# Slave_BMS_ESKD.net
KiCad netlist of a schematic drawn in EAGLE
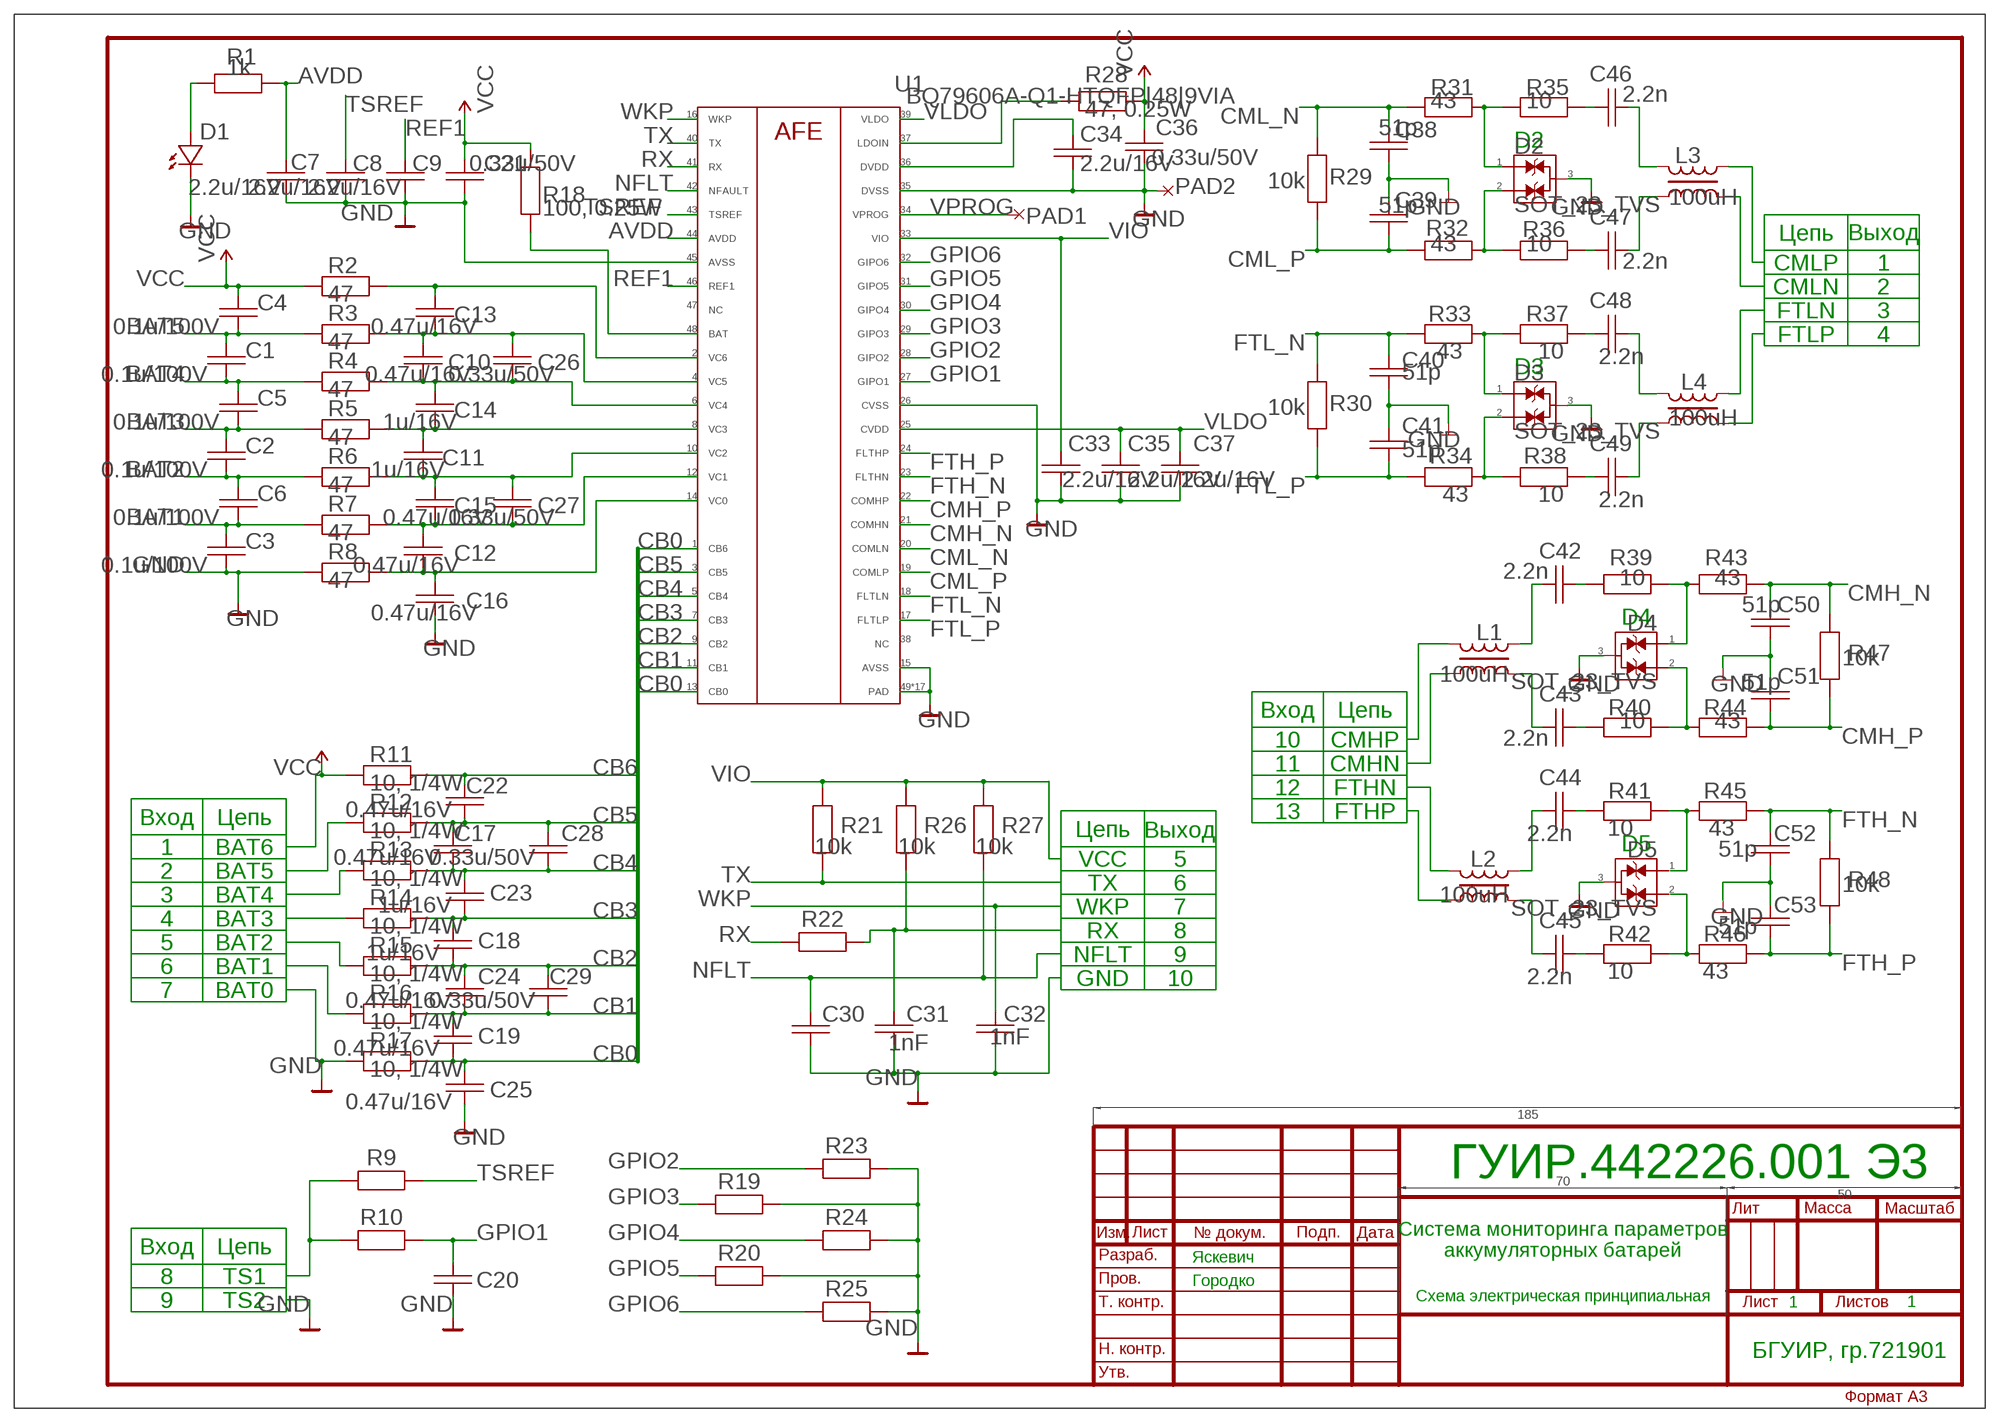
[diagram p0: schematic, sheet 1]

(export (version "E")
  (design (tool "Eeschema 10.0.6"))
  (components
    (comp (ref "C1")
      (value "0.1u/100V")
      (footprint "eagle-import:C1206")
      (libsource (lib "eagle-import") (part "ESCD_CAP"))
    )
    (comp (ref "C2")
      (value "0.1u/100V")
      (footprint "eagle-import:C1206")
      (libsource (lib "eagle-import") (part "ESCD_CAP"))
    )
    (comp (ref "C3")
      (value "0.1u/100V")
      (footprint "eagle-import:C1206")
      (libsource (lib "eagle-import") (part "ESCD_CAP"))
    )
    (comp (ref "C4")
      (value "0.1u/100V")
      (footprint "eagle-import:C1206")
      (libsource (lib "eagle-import") (part "ESCD_CAP"))
    )
    (comp (ref "C5")
      (value "0.1u/100V")
      (footprint "eagle-import:C1206")
      (libsource (lib "eagle-import") (part "ESCD_CAP"))
    )
    (comp (ref "C6")
      (value "0.1u/100V")
      (footprint "eagle-import:C1206")
      (libsource (lib "eagle-import") (part "ESCD_CAP"))
    )
    (comp (ref "C7")
      (value "2.2u/16V")
      (footprint "eagle-import:C1206")
      (libsource (lib "eagle-import") (part "ESCD_CAP"))
    )
    (comp (ref "C8")
      (value "2.2u/16V")
      (footprint "eagle-import:C1206")
      (libsource (lib "eagle-import") (part "ESCD_CAP"))
    )
    (comp (ref "C9")
      (value "2.2u/16V")
      (footprint "eagle-import:C1206")
      (libsource (lib "eagle-import") (part "ESCD_CAP"))
    )
    (comp (ref "C10")
      (value "0.47u/16V")
      (footprint "eagle-import:C1206")
      (libsource (lib "eagle-import") (part "ESCD_CAP"))
    )
    (comp (ref "C11")
      (value "1u/16V")
      (footprint "eagle-import:C1206")
      (libsource (lib "eagle-import") (part "ESCD_CAP"))
    )
    (comp (ref "C12")
      (value "0.47u/16V")
      (footprint "eagle-import:C1206")
      (libsource (lib "eagle-import") (part "ESCD_CAP"))
    )
    (comp (ref "C13")
      (value "0.47u/16V")
      (footprint "eagle-import:C1206")
      (libsource (lib "eagle-import") (part "ESCD_CAP"))
    )
    (comp (ref "C14")
      (value "1u/16V")
      (footprint "eagle-import:C1206")
      (libsource (lib "eagle-import") (part "ESCD_CAP"))
    )
    (comp (ref "C15")
      (value "0.47u/16V")
      (footprint "eagle-import:C1206")
      (libsource (lib "eagle-import") (part "ESCD_CAP"))
    )
    (comp (ref "C16")
      (value "0.47u/16V")
      (footprint "eagle-import:C1206")
      (libsource (lib "eagle-import") (part "ESCD_CAP"))
    )
    (comp (ref "C17")
      (value "0.47u/16V")
      (footprint "eagle-import:C1206")
      (libsource (lib "eagle-import") (part "ESCD_CAP"))
    )
    (comp (ref "C18")
      (value "1u/16V")
      (footprint "eagle-import:C1206")
      (libsource (lib "eagle-import") (part "ESCD_CAP"))
    )
    (comp (ref "C19")
      (value "0.47u/16V")
      (footprint "eagle-import:C1206")
      (libsource (lib "eagle-import") (part "ESCD_CAP"))
    )
    (comp (ref "C20")
      (value "ESCD_CAP")
      (footprint "eagle-import:C1206")
      (libsource (lib "eagle-import") (part "ESCD_CAP"))
    )
    (comp (ref "C21")
      (value "0.33u/50V")
      (footprint "eagle-import:C1206")
      (libsource (lib "eagle-import") (part "ESCD_CAP"))
    )
    (comp (ref "C22")
      (value "0.47u/16V")
      (footprint "eagle-import:C1206")
      (libsource (lib "eagle-import") (part "ESCD_CAP"))
    )
    (comp (ref "C23")
      (value "1u/16V")
      (footprint "eagle-import:C1206")
      (libsource (lib "eagle-import") (part "ESCD_CAP"))
    )
    (comp (ref "C24")
      (value "0.47u/16V")
      (footprint "eagle-import:C1206")
      (libsource (lib "eagle-import") (part "ESCD_CAP"))
    )
    (comp (ref "C25")
      (value "0.47u/16V")
      (footprint "eagle-import:C1206")
      (libsource (lib "eagle-import") (part "ESCD_CAP"))
    )
    (comp (ref "C26")
      (value "0.33u/50V")
      (footprint "eagle-import:C1206")
      (libsource (lib "eagle-import") (part "ESCD_CAP"))
    )
    (comp (ref "C27")
      (value "0.33u/50V")
      (footprint "eagle-import:C1206")
      (libsource (lib "eagle-import") (part "ESCD_CAP"))
    )
    (comp (ref "C28")
      (value "0.33u/50V")
      (footprint "eagle-import:C1206")
      (libsource (lib "eagle-import") (part "ESCD_CAP"))
    )
    (comp (ref "C29")
      (value "0.33u/50V")
      (footprint "eagle-import:C1206")
      (libsource (lib "eagle-import") (part "ESCD_CAP"))
    )
    (comp (ref "C30")
      (value "ESCD_CAP")
      (footprint "eagle-import:C1206")
      (libsource (lib "eagle-import") (part "ESCD_CAP"))
    )
    (comp (ref "C31")
      (value "1nF")
      (footprint "eagle-import:C1206")
      (libsource (lib "eagle-import") (part "ESCD_CAP"))
    )
    (comp (ref "C32")
      (value "1nF")
      (footprint "eagle-import:C1206")
      (libsource (lib "eagle-import") (part "ESCD_CAP"))
    )
    (comp (ref "C33")
      (value "2.2u/16V")
      (footprint "eagle-import:C1206")
      (libsource (lib "eagle-import") (part "ESCD_CAP"))
    )
    (comp (ref "C34")
      (value "2.2u/16V")
      (footprint "eagle-import:C1206")
      (libsource (lib "eagle-import") (part "ESCD_CAP"))
    )
    (comp (ref "C35")
      (value "2.2u/16V")
      (footprint "eagle-import:C1206")
      (libsource (lib "eagle-import") (part "ESCD_CAP"))
    )
    (comp (ref "C36")
      (value "0.33u/50V")
      (footprint "eagle-import:C1206")
      (libsource (lib "eagle-import") (part "ESCD_CAP"))
    )
    (comp (ref "C37")
      (value "2.2u/16V")
      (footprint "eagle-import:C1206")
      (libsource (lib "eagle-import") (part "ESCD_CAP"))
    )
    (comp (ref "C38")
      (value "51p")
      (footprint "eagle-import:C1206")
      (libsource (lib "eagle-import") (part "ESCD_CAP"))
    )
    (comp (ref "C39")
      (value "51p")
      (footprint "eagle-import:C1206")
      (libsource (lib "eagle-import") (part "ESCD_CAP"))
    )
    (comp (ref "C40")
      (value "51p")
      (footprint "eagle-import:C1206")
      (libsource (lib "eagle-import") (part "ESCD_CAP"))
    )
    (comp (ref "C41")
      (value "51p")
      (footprint "eagle-import:C1206")
      (libsource (lib "eagle-import") (part "ESCD_CAP"))
    )
    (comp (ref "C42")
      (value "2.2n")
      (footprint "eagle-import:C1206")
      (libsource (lib "eagle-import") (part "ESCD_CAP"))
    )
    (comp (ref "C43")
      (value "2.2n")
      (footprint "eagle-import:C1206")
      (libsource (lib "eagle-import") (part "ESCD_CAP"))
    )
    (comp (ref "C44")
      (value "2.2n")
      (footprint "eagle-import:C1206")
      (libsource (lib "eagle-import") (part "ESCD_CAP"))
    )
    (comp (ref "C45")
      (value "2.2n")
      (footprint "eagle-import:C1206")
      (libsource (lib "eagle-import") (part "ESCD_CAP"))
    )
    (comp (ref "C46")
      (value "2.2n")
      (footprint "eagle-import:C1206")
      (libsource (lib "eagle-import") (part "ESCD_CAP"))
    )
    (comp (ref "C47")
      (value "2.2n")
      (footprint "eagle-import:C1206")
      (libsource (lib "eagle-import") (part "ESCD_CAP"))
    )
    (comp (ref "C48")
      (value "2.2n")
      (footprint "eagle-import:C1206")
      (libsource (lib "eagle-import") (part "ESCD_CAP"))
    )
    (comp (ref "C49")
      (value "2.2n")
      (footprint "eagle-import:C1206")
      (libsource (lib "eagle-import") (part "ESCD_CAP"))
    )
    (comp (ref "C50")
      (value "51p")
      (footprint "eagle-import:C1206")
      (libsource (lib "eagle-import") (part "ESCD_CAP"))
    )
    (comp (ref "C51")
      (value "51p")
      (footprint "eagle-import:C1206")
      (libsource (lib "eagle-import") (part "ESCD_CAP"))
    )
    (comp (ref "C52")
      (value "51p")
      (footprint "eagle-import:C1206")
      (libsource (lib "eagle-import") (part "ESCD_CAP"))
    )
    (comp (ref "C53")
      (value "51p")
      (footprint "eagle-import:C1206")
      (libsource (lib "eagle-import") (part "ESCD_CAP"))
    )
    (comp (ref "D1")
      (value "ESCD_LED")
      (footprint "eagle-import:SOD106A")
      (fields (field (name "MPN") "BYS10/45"))
      (libsource (lib "eagle-import") (part "ESCD_LED"))
    )
    (comp (ref "D2")
      (value "SOT_23_TVS")
      (footprint "eagle-import:SOT23")
      (libsource (lib "eagle-import") (part "SOT_23_TVS"))
    )
    (comp (ref "D3")
      (value "SOT_23_TVS")
      (footprint "eagle-import:SOT23")
      (libsource (lib "eagle-import") (part "SOT_23_TVS"))
    )
    (comp (ref "D4")
      (value "SOT_23_TVS")
      (footprint "eagle-import:SOT23")
      (libsource (lib "eagle-import") (part "SOT_23_TVS"))
    )
    (comp (ref "D5")
      (value "SOT_23_TVS")
      (footprint "eagle-import:SOT23")
      (libsource (lib "eagle-import") (part "SOT_23_TVS"))
    )
    (comp (ref "L1")
      (value "100uH")
      (footprint "eagle-import:ACT45B")
      (libsource (lib "eagle-import") (part "TDK_ACT45BIND_BOURNS_SRF4532-M"))
    )
    (comp (ref "L2")
      (value "100uH")
      (footprint "eagle-import:ACT45B")
      (libsource (lib "eagle-import") (part "TDK_ACT45BIND_BOURNS_SRF4532-M"))
    )
    (comp (ref "L3")
      (value "100uH")
      (footprint "eagle-import:ACT45B")
      (libsource (lib "eagle-import") (part "TDK_ACT45BIND_BOURNS_SRF4532-M"))
    )
    (comp (ref "L4")
      (value "100uH")
      (footprint "eagle-import:ACT45B")
      (libsource (lib "eagle-import") (part "TDK_ACT45BIND_BOURNS_SRF4532-M"))
    )
    (comp (ref "PAD1")
      (value "SMD_PAD")
      (footprint "eagle-import:SMD_PAD")
      (libsource (lib "eagle-import") (part "SMD_PAD"))
    )
    (comp (ref "PAD2")
      (value "SMD_PAD")
      (footprint "eagle-import:SMD_PAD")
      (libsource (lib "eagle-import") (part "SMD_PAD"))
    )
    (comp (ref "R1")
      (value "1k")
      (footprint "eagle-import:R1206")
      (libsource (lib "eagle-import") (part "ESCD_RES"))
    )
    (comp (ref "R2")
      (value "47")
      (footprint "eagle-import:R1206")
      (libsource (lib "eagle-import") (part "ESCD_RES"))
    )
    (comp (ref "R3")
      (value "47")
      (footprint "eagle-import:R1206")
      (libsource (lib "eagle-import") (part "ESCD_RES"))
    )
    (comp (ref "R4")
      (value "47")
      (footprint "eagle-import:R1206")
      (libsource (lib "eagle-import") (part "ESCD_RES"))
    )
    (comp (ref "R5")
      (value "47")
      (footprint "eagle-import:R1206")
      (libsource (lib "eagle-import") (part "ESCD_RES"))
    )
    (comp (ref "R6")
      (value "47")
      (footprint "eagle-import:R1206")
      (libsource (lib "eagle-import") (part "ESCD_RES"))
    )
    (comp (ref "R7")
      (value "47")
      (footprint "eagle-import:R1206")
      (libsource (lib "eagle-import") (part "ESCD_RES"))
    )
    (comp (ref "R8")
      (value "47")
      (footprint "eagle-import:R1206")
      (libsource (lib "eagle-import") (part "ESCD_RES"))
    )
    (comp (ref "R9")
      (value "ESCD_RES")
      (footprint "eagle-import:R1206")
      (libsource (lib "eagle-import") (part "ESCD_RES"))
    )
    (comp (ref "R10")
      (value "ESCD_RES")
      (footprint "eagle-import:R1206")
      (libsource (lib "eagle-import") (part "ESCD_RES"))
    )
    (comp (ref "R11")
      (value "10, 1/4W")
      (footprint "eagle-import:R1206")
      (libsource (lib "eagle-import") (part "ESCD_RES"))
    )
    (comp (ref "R12")
      (value "10, 1/4W")
      (footprint "eagle-import:R1206")
      (libsource (lib "eagle-import") (part "ESCD_RES"))
    )
    (comp (ref "R13")
      (value "10, 1/4W")
      (footprint "eagle-import:R1206")
      (libsource (lib "eagle-import") (part "ESCD_RES"))
    )
    (comp (ref "R14")
      (value "10, 1/4W")
      (footprint "eagle-import:R1206")
      (libsource (lib "eagle-import") (part "ESCD_RES"))
    )
    (comp (ref "R15")
      (value "10, 1/4W")
      (footprint "eagle-import:R1206")
      (libsource (lib "eagle-import") (part "ESCD_RES"))
    )
    (comp (ref "R16")
      (value "10, 1/4W")
      (footprint "eagle-import:R1206")
      (libsource (lib "eagle-import") (part "ESCD_RES"))
    )
    (comp (ref "R17")
      (value "10, 1/4W")
      (footprint "eagle-import:R1206")
      (libsource (lib "eagle-import") (part "ESCD_RES"))
    )
    (comp (ref "R18")
      (value "100, 0.25W")
      (footprint "eagle-import:R1206")
      (libsource (lib "eagle-import") (part "ESCD_RES"))
    )
    (comp (ref "R19")
      (value "ESCD_RES")
      (footprint "eagle-import:R1206")
      (libsource (lib "eagle-import") (part "ESCD_RES"))
    )
    (comp (ref "R20")
      (value "ESCD_RES")
      (footprint "eagle-import:R1206")
      (libsource (lib "eagle-import") (part "ESCD_RES"))
    )
    (comp (ref "R21")
      (value "10k")
      (footprint "eagle-import:R1206")
      (libsource (lib "eagle-import") (part "ESCD_RES"))
    )
    (comp (ref "R22")
      (value "ESCD_RES")
      (footprint "eagle-import:R1206")
      (libsource (lib "eagle-import") (part "ESCD_RES"))
    )
    (comp (ref "R23")
      (value "ESCD_RES")
      (footprint "eagle-import:R1206")
      (libsource (lib "eagle-import") (part "ESCD_RES"))
    )
    (comp (ref "R24")
      (value "ESCD_RES")
      (footprint "eagle-import:R1206")
      (libsource (lib "eagle-import") (part "ESCD_RES"))
    )
    (comp (ref "R25")
      (value "ESCD_RES")
      (footprint "eagle-import:R1206")
      (libsource (lib "eagle-import") (part "ESCD_RES"))
    )
    (comp (ref "R26")
      (value "10k")
      (footprint "eagle-import:R1206")
      (libsource (lib "eagle-import") (part "ESCD_RES"))
    )
    (comp (ref "R27")
      (value "10k")
      (footprint "eagle-import:R1206")
      (libsource (lib "eagle-import") (part "ESCD_RES"))
    )
    (comp (ref "R28")
      (value "47, 0.25W")
      (footprint "eagle-import:R1206")
      (libsource (lib "eagle-import") (part "ESCD_RES"))
    )
    (comp (ref "R29")
      (value "10k")
      (footprint "eagle-import:R1206")
      (libsource (lib "eagle-import") (part "ESCD_RES"))
    )
    (comp (ref "R30")
      (value "10k")
      (footprint "eagle-import:R1206")
      (libsource (lib "eagle-import") (part "ESCD_RES"))
    )
    (comp (ref "R31")
      (value "43")
      (footprint "eagle-import:R1206")
      (libsource (lib "eagle-import") (part "ESCD_RES"))
    )
    (comp (ref "R32")
      (value "43")
      (footprint "eagle-import:R1206")
      (libsource (lib "eagle-import") (part "ESCD_RES"))
    )
    (comp (ref "R33")
      (value "43")
      (footprint "eagle-import:R1206")
      (libsource (lib "eagle-import") (part "ESCD_RES"))
    )
    (comp (ref "R34")
      (value "43")
      (footprint "eagle-import:R1206")
      (libsource (lib "eagle-import") (part "ESCD_RES"))
    )
    (comp (ref "R35")
      (value "10")
      (footprint "eagle-import:R1206")
      (libsource (lib "eagle-import") (part "ESCD_RES"))
    )
    (comp (ref "R36")
      (value "10")
      (footprint "eagle-import:R1206")
      (libsource (lib "eagle-import") (part "ESCD_RES"))
    )
    (comp (ref "R37")
      (value "10")
      (footprint "eagle-import:R1206")
      (libsource (lib "eagle-import") (part "ESCD_RES"))
    )
    (comp (ref "R38")
      (value "10")
      (footprint "eagle-import:R1206")
      (libsource (lib "eagle-import") (part "ESCD_RES"))
    )
    (comp (ref "R39")
      (value "10")
      (footprint "eagle-import:R1206")
      (libsource (lib "eagle-import") (part "ESCD_RES"))
    )
    (comp (ref "R40")
      (value "10")
      (footprint "eagle-import:R1206")
      (libsource (lib "eagle-import") (part "ESCD_RES"))
    )
    (comp (ref "R41")
      (value "10")
      (footprint "eagle-import:R1206")
      (libsource (lib "eagle-import") (part "ESCD_RES"))
    )
    (comp (ref "R42")
      (value "10")
      (footprint "eagle-import:R1206")
      (libsource (lib "eagle-import") (part "ESCD_RES"))
    )
    (comp (ref "R43")
      (value "43")
      (footprint "eagle-import:R1206")
      (libsource (lib "eagle-import") (part "ESCD_RES"))
    )
    (comp (ref "R44")
      (value "43")
      (footprint "eagle-import:R1206")
      (libsource (lib "eagle-import") (part "ESCD_RES"))
    )
    (comp (ref "R45")
      (value "43")
      (footprint "eagle-import:R1206")
      (libsource (lib "eagle-import") (part "ESCD_RES"))
    )
    (comp (ref "R46")
      (value "43")
      (footprint "eagle-import:R1206")
      (libsource (lib "eagle-import") (part "ESCD_RES"))
    )
    (comp (ref "R47")
      (value "10k")
      (footprint "eagle-import:R1206")
      (libsource (lib "eagle-import") (part "ESCD_RES"))
    )
    (comp (ref "R48")
      (value "10k")
      (footprint "eagle-import:R1206")
      (libsource (lib "eagle-import") (part "ESCD_RES"))
    )
    (comp (ref "U1")
      (value "BQ79606A-Q1-HTQFP|48|9VIA")
      (footprint "eagle-import:HTQFP48-9X9MM-VIA")
      (libsource (lib "eagle-import") (part "BQ79606A-Q1-HTQFP|48|9VIA"))
    )
  )
  (nets
    (net (code "1") (name "/AVDD") (class "Default")
      (node (ref "C7") (pin "1") (pinfunction "1_1") (pintype "passive"))
      (node (ref "R1") (pin "2") (pinfunction "2_2") (pintype "passive"))
      (node (ref "U1") (pin "44") (pinfunction "AVDD_44") (pintype "output"))
    )
    (net (code "2") (name "/BAT1") (class "Default")
      (node (ref "C3") (pin "2") (pinfunction "2_2") (pintype "passive"))
      (node (ref "C6") (pin "1") (pinfunction "1_1") (pintype "passive"))
      (node (ref "R16") (pin "1") (pinfunction "1_1") (pintype "passive"))
      (node (ref "R7") (pin "1") (pinfunction "1_1") (pintype "passive"))
    )
    (net (code "3") (name "/BAT2") (class "Default")
      (node (ref "C2") (pin "1") (pinfunction "1_1") (pintype "passive"))
      (node (ref "C6") (pin "2") (pinfunction "2_2") (pintype "passive"))
      (node (ref "R15") (pin "1") (pinfunction "1_1") (pintype "passive"))
      (node (ref "R6") (pin "1") (pinfunction "1_1") (pintype "passive"))
    )
    (net (code "4") (name "/BAT3") (class "Default")
      (node (ref "C2") (pin "2") (pinfunction "2_2") (pintype "passive"))
      (node (ref "C5") (pin "1") (pinfunction "1_1") (pintype "passive"))
      (node (ref "R14") (pin "1") (pinfunction "1_1") (pintype "passive"))
      (node (ref "R5") (pin "1") (pinfunction "1_1") (pintype "passive"))
    )
    (net (code "5") (name "/BAT4") (class "Default")
      (node (ref "C1") (pin "1") (pinfunction "1_1") (pintype "passive"))
      (node (ref "C5") (pin "2") (pinfunction "2_2") (pintype "passive"))
      (node (ref "R13") (pin "1") (pinfunction "1_1") (pintype "passive"))
      (node (ref "R4") (pin "1") (pinfunction "1_1") (pintype "passive"))
    )
    (net (code "6") (name "/BAT5") (class "Default")
      (node (ref "C1") (pin "2") (pinfunction "2_2") (pintype "passive"))
      (node (ref "C4") (pin "1") (pinfunction "1_1") (pintype "passive"))
      (node (ref "R12") (pin "1") (pinfunction "1_1") (pintype "passive"))
      (node (ref "R3") (pin "1") (pinfunction "1_1") (pintype "passive"))
    )
    (net (code "7") (name "/CB0") (class "Default")
      (node (ref "C19") (pin "1") (pinfunction "1_1") (pintype "passive"))
      (node (ref "C25") (pin "2") (pinfunction "2_2") (pintype "passive"))
      (node (ref "R17") (pin "2") (pinfunction "2_2") (pintype "passive"))
      (node (ref "U1") (pin "1") (pinfunction "CB6_1") (pintype "bidirectional"))
      (node (ref "U1") (pin "13") (pinfunction "CB0_13") (pintype "bidirectional"))
    )
    (net (code "8") (name "/CB1") (class "Default")
      (node (ref "C19") (pin "2") (pinfunction "2_2") (pintype "passive"))
      (node (ref "C24") (pin "1") (pinfunction "1_1") (pintype "passive"))
      (node (ref "C29") (pin "1") (pinfunction "1_1") (pintype "passive"))
      (node (ref "R16") (pin "2") (pinfunction "2_2") (pintype "passive"))
      (node (ref "U1") (pin "11") (pinfunction "CB1_11") (pintype "bidirectional"))
    )
    (net (code "9") (name "/CB2") (class "Default")
      (node (ref "C18") (pin "1") (pinfunction "1_1") (pintype "passive"))
      (node (ref "C24") (pin "2") (pinfunction "2_2") (pintype "passive"))
      (node (ref "C29") (pin "2") (pinfunction "2_2") (pintype "passive"))
      (node (ref "R15") (pin "2") (pinfunction "2_2") (pintype "passive"))
      (node (ref "U1") (pin "9") (pinfunction "CB2_9") (pintype "bidirectional"))
    )
    (net (code "10") (name "/CB3") (class "Default")
      (node (ref "C18") (pin "2") (pinfunction "2_2") (pintype "passive"))
      (node (ref "C23") (pin "1") (pinfunction "1_1") (pintype "passive"))
      (node (ref "R14") (pin "2") (pinfunction "2_2") (pintype "passive"))
      (node (ref "U1") (pin "7") (pinfunction "CB3_7") (pintype "bidirectional"))
    )
    (net (code "11") (name "/CB4") (class "Default")
      (node (ref "C17") (pin "1") (pinfunction "1_1") (pintype "passive"))
      (node (ref "C23") (pin "2") (pinfunction "2_2") (pintype "passive"))
      (node (ref "C28") (pin "1") (pinfunction "1_1") (pintype "passive"))
      (node (ref "R13") (pin "2") (pinfunction "2_2") (pintype "passive"))
      (node (ref "U1") (pin "5") (pinfunction "CB4_5") (pintype "bidirectional"))
    )
    (net (code "12") (name "/CB5") (class "Default")
      (node (ref "C17") (pin "2") (pinfunction "2_2") (pintype "passive"))
      (node (ref "C22") (pin "1") (pinfunction "1_1") (pintype "passive"))
      (node (ref "C28") (pin "2") (pinfunction "2_2") (pintype "passive"))
      (node (ref "R12") (pin "2") (pinfunction "2_2") (pintype "passive"))
      (node (ref "U1") (pin "3") (pinfunction "CB5_3") (pintype "bidirectional"))
    )
    (net (code "13") (name "/CB6") (class "Default")
      (node (ref "C22") (pin "2") (pinfunction "2_2") (pintype "passive"))
      (node (ref "R11") (pin "2") (pinfunction "2_2") (pintype "passive"))
    )
    (net (code "14") (name "/CMH_N") (class "Default")
      (node (ref "C50") (pin "2") (pinfunction "2_2") (pintype "passive"))
      (node (ref "R43") (pin "1") (pinfunction "1_1") (pintype "passive"))
      (node (ref "R47") (pin "1") (pinfunction "1_1") (pintype "passive"))
      (node (ref "U1") (pin "21") (pinfunction "COMHN_21") (pintype "input"))
    )
    (net (code "15") (name "/CMH_P") (class "Default")
      (node (ref "C51") (pin "2") (pinfunction "2_2") (pintype "passive"))
      (node (ref "R44") (pin "1") (pinfunction "1_1") (pintype "passive"))
      (node (ref "R47") (pin "2") (pinfunction "2_2") (pintype "passive"))
      (node (ref "U1") (pin "22") (pinfunction "COMHP_22") (pintype "input"))
    )
    (net (code "16") (name "/CML_N") (class "Default")
      (node (ref "C38") (pin "2") (pinfunction "2_2") (pintype "passive"))
      (node (ref "R29") (pin "1") (pinfunction "1_1") (pintype "passive"))
      (node (ref "R31") (pin "1") (pinfunction "1_1") (pintype "passive"))
      (node (ref "U1") (pin "20") (pinfunction "COMLN_20") (pintype "output"))
    )
    (net (code "17") (name "/CML_P") (class "Default")
      (node (ref "C39") (pin "2") (pinfunction "2_2") (pintype "passive"))
      (node (ref "R29") (pin "2") (pinfunction "2_2") (pintype "passive"))
      (node (ref "R32") (pin "1") (pinfunction "1_1") (pintype "passive"))
      (node (ref "U1") (pin "19") (pinfunction "COMLP_19") (pintype "output"))
    )
    (net (code "18") (name "/FTH_N") (class "Default")
      (node (ref "C52") (pin "2") (pinfunction "2_2") (pintype "passive"))
      (node (ref "R45") (pin "1") (pinfunction "1_1") (pintype "passive"))
      (node (ref "R48") (pin "1") (pinfunction "1_1") (pintype "passive"))
      (node (ref "U1") (pin "23") (pinfunction "FLTHN_23") (pintype "input"))
    )
    (net (code "19") (name "/FTH_P") (class "Default")
      (node (ref "C53") (pin "2") (pinfunction "2_2") (pintype "passive"))
      (node (ref "R46") (pin "1") (pinfunction "1_1") (pintype "passive"))
      (node (ref "R48") (pin "2") (pinfunction "2_2") (pintype "passive"))
      (node (ref "U1") (pin "24") (pinfunction "FLTHP_24") (pintype "input"))
    )
    (net (code "20") (name "/FTL_N") (class "Default")
      (node (ref "C40") (pin "2") (pinfunction "2_2") (pintype "passive"))
      (node (ref "R30") (pin "1") (pinfunction "1_1") (pintype "passive"))
      (node (ref "R33") (pin "1") (pinfunction "1_1") (pintype "passive"))
      (node (ref "U1") (pin "18") (pinfunction "FLTLN_18") (pintype "output"))
    )
    (net (code "21") (name "/FTL_P") (class "Default")
      (node (ref "C41") (pin "2") (pinfunction "2_2") (pintype "passive"))
      (node (ref "R30") (pin "2") (pinfunction "2_2") (pintype "passive"))
      (node (ref "R34") (pin "1") (pinfunction "1_1") (pintype "passive"))
      (node (ref "U1") (pin "17") (pinfunction "FLTLP_17") (pintype "output"))
    )
    (net (code "22") (name "/GPIO1") (class "Default")
      (node (ref "C20") (pin "1") (pinfunction "1_1") (pintype "passive"))
      (node (ref "R10") (pin "2") (pinfunction "2_2") (pintype "passive"))
      (node (ref "U1") (pin "27") (pinfunction "GIPO1_27") (pintype "bidirectional"))
    )
    (net (code "23") (name "/GPIO2") (class "Default")
      (node (ref "R23") (pin "1") (pinfunction "1_1") (pintype "passive"))
      (node (ref "U1") (pin "28") (pinfunction "GIPO2_28") (pintype "bidirectional"))
    )
    (net (code "24") (name "/GPIO3") (class "Default")
      (node (ref "R19") (pin "1") (pinfunction "1_1") (pintype "passive"))
      (node (ref "U1") (pin "29") (pinfunction "GIPO3_29") (pintype "bidirectional"))
    )
    (net (code "25") (name "/GPIO4") (class "Default")
      (node (ref "R24") (pin "1") (pinfunction "1_1") (pintype "passive"))
      (node (ref "U1") (pin "30") (pinfunction "GIPO4_30") (pintype "bidirectional"))
    )
    (net (code "26") (name "/GPIO5") (class "Default")
      (node (ref "R20") (pin "1") (pinfunction "1_1") (pintype "passive"))
      (node (ref "U1") (pin "31") (pinfunction "GIPO5_31") (pintype "bidirectional"))
    )
    (net (code "27") (name "/GPIO6") (class "Default")
      (node (ref "R25") (pin "1") (pinfunction "1_1") (pintype "passive"))
      (node (ref "U1") (pin "32") (pinfunction "GIPO6_32") (pintype "bidirectional"))
    )
    (net (code "28") (name "/NFLT") (class "Default")
      (node (ref "C30") (pin "1") (pinfunction "1_1") (pintype "passive"))
      (node (ref "R27") (pin "1") (pinfunction "1_1") (pintype "passive"))
      (node (ref "U1") (pin "42") (pinfunction "NFAULT_42") (pintype "output"))
    )
    (net (code "29") (name "/REF1") (class "Default")
      (node (ref "C9") (pin "1") (pinfunction "1_1") (pintype "passive"))
      (node (ref "U1") (pin "46") (pinfunction "REF1_46") (pintype "output"))
    )
    (net (code "30") (name "/RX") (class "Default")
      (node (ref "R22") (pin "1") (pinfunction "1_1") (pintype "passive"))
      (node (ref "U1") (pin "41") (pinfunction "RX_41") (pintype "input"))
    )
    (net (code "31") (name "/TSREF") (class "Default")
      (node (ref "C8") (pin "1") (pinfunction "1_1") (pintype "passive"))
      (node (ref "R9") (pin "2") (pinfunction "2_2") (pintype "passive"))
      (node (ref "U1") (pin "43") (pinfunction "TSREF_43") (pintype "output"))
    )
    (net (code "32") (name "/TX") (class "Default")
      (node (ref "R21") (pin "1") (pinfunction "1_1") (pintype "passive"))
      (node (ref "U1") (pin "40") (pinfunction "TX_40") (pintype "output"))
    )
    (net (code "33") (name "/VIO") (class "Default")
      (node (ref "C33") (pin "1") (pinfunction "1_1") (pintype "passive"))
      (node (ref "R21") (pin "2") (pinfunction "2_2") (pintype "passive"))
      (node (ref "R26") (pin "2") (pinfunction "2_2") (pintype "passive"))
      (node (ref "R27") (pin "2") (pinfunction "2_2") (pintype "passive"))
      (node (ref "U1") (pin "33") (pinfunction "VIO_33") (pintype "input"))
    )
    (net (code "34") (name "/VLDO") (class "Default")
      (node (ref "C35") (pin "1") (pinfunction "1_1") (pintype "passive"))
      (node (ref "C37") (pin "1") (pinfunction "1_1") (pintype "passive"))
      (node (ref "U1") (pin "25") (pinfunction "CVDD_25") (pintype "power_in"))
      (node (ref "U1") (pin "39") (pinfunction "VLDO_39") (pintype "output"))
    )
    (net (code "35") (name "/VPROG") (class "Default")
      (node (ref "PAD1") (pin "1") (pinfunction "P_1") (pintype "passive"))
      (node (ref "U1") (pin "34") (pinfunction "VPROG_34") (pintype "input"))
    )
    (net (code "36") (name "/WKP") (class "Default")
      (node (ref "C32") (pin "2") (pinfunction "2_2") (pintype "passive"))
      (node (ref "U1") (pin "16") (pinfunction "WKP_16") (pintype "input"))
    )
    (net (code "37") (name "GND") (class "Default")
      (node (ref "C16") (pin "1") (pinfunction "1_1") (pintype "passive"))
      (node (ref "C20") (pin "2") (pinfunction "2_2") (pintype "passive"))
      (node (ref "C21") (pin "2") (pinfunction "2_2") (pintype "passive"))
      (node (ref "C25") (pin "1") (pinfunction "1_1") (pintype "passive"))
      (node (ref "C3") (pin "1") (pinfunction "1_1") (pintype "passive"))
      (node (ref "C30") (pin "2") (pinfunction "2_2") (pintype "passive"))
      (node (ref "C31") (pin "1") (pinfunction "1_1") (pintype "passive"))
      (node (ref "C32") (pin "1") (pinfunction "1_1") (pintype "passive"))
      (node (ref "C33") (pin "2") (pinfunction "2_2") (pintype "passive"))
      (node (ref "C34") (pin "2") (pinfunction "2_2") (pintype "passive"))
      (node (ref "C35") (pin "2") (pinfunction "2_2") (pintype "passive"))
      (node (ref "C36") (pin "2") (pinfunction "2_2") (pintype "passive"))
      (node (ref "C37") (pin "2") (pinfunction "2_2") (pintype "passive"))
      (node (ref "C38") (pin "1") (pinfunction "1_1") (pintype "passive"))
      (node (ref "C39") (pin "1") (pinfunction "1_1") (pintype "passive"))
      (node (ref "C40") (pin "1") (pinfunction "1_1") (pintype "passive"))
      (node (ref "C41") (pin "1") (pinfunction "1_1") (pintype "passive"))
      (node (ref "C50") (pin "1") (pinfunction "1_1") (pintype "passive"))
      (node (ref "C51") (pin "1") (pinfunction "1_1") (pintype "passive"))
      (node (ref "C52") (pin "1") (pinfunction "1_1") (pintype "passive"))
      (node (ref "C53") (pin "1") (pinfunction "1_1") (pintype "passive"))
      (node (ref "C7") (pin "2") (pinfunction "2_2") (pintype "passive"))
      (node (ref "C8") (pin "2") (pinfunction "2_2") (pintype "passive"))
      (node (ref "C9") (pin "2") (pinfunction "2_2") (pintype "passive"))
      (node (ref "D1") (pin "K") (pinfunction "K_K") (pintype "passive"))
      (node (ref "D2") (pin "3") (pinfunction "3_3") (pintype "passive"))
      (node (ref "D3") (pin "3") (pinfunction "3_3") (pintype "passive"))
      (node (ref "D4") (pin "3") (pinfunction "3_3") (pintype "passive"))
      (node (ref "D5") (pin "3") (pinfunction "3_3") (pintype "passive"))
      (node (ref "PAD2") (pin "1") (pinfunction "P_1") (pintype "passive"))
      (node (ref "R17") (pin "1") (pinfunction "1_1") (pintype "passive"))
      (node (ref "R19") (pin "2") (pinfunction "2_2") (pintype "passive"))
      (node (ref "R20") (pin "2") (pinfunction "2_2") (pintype "passive"))
      (node (ref "R23") (pin "2") (pinfunction "2_2") (pintype "passive"))
      (node (ref "R24") (pin "2") (pinfunction "2_2") (pintype "passive"))
      (node (ref "R25") (pin "2") (pinfunction "2_2") (pintype "passive"))
      (node (ref "R8") (pin "1") (pinfunction "1_1") (pintype "passive"))
      (node (ref "U1") (pin "15") (pinfunction "AVSS_15") (pintype "power_in"))
      (node (ref "U1") (pin "26") (pinfunction "CVSS_26") (pintype "power_in"))
      (node (ref "U1") (pin "35") (pinfunction "DVSS_35") (pintype "power_in"))
      (node (ref "U1") (pin "45") (pinfunction "AVSS_45") (pintype "power_in"))
      (node (ref "U1") (pin "49") (pinfunction "PAD_49") (pintype "power_in"))
      (node (ref "U1") (pin "491") (pinfunction "PAD_491") (pintype "power_in"))
      (node (ref "U1") (pin "492") (pinfunction "PAD_492") (pintype "power_in"))
      (node (ref "U1") (pin "493") (pinfunction "PAD_493") (pintype "power_in"))
      (node (ref "U1") (pin "494") (pinfunction "PAD_494") (pintype "power_in"))
      (node (ref "U1") (pin "495") (pinfunction "PAD_495") (pintype "power_in"))
      (node (ref "U1") (pin "496") (pinfunction "PAD_496") (pintype "power_in"))
      (node (ref "U1") (pin "497") (pinfunction "PAD_497") (pintype "power_in"))
      (node (ref "U1") (pin "498") (pinfunction "PAD_498") (pintype "power_in"))
      (node (ref "U1") (pin "499") (pinfunction "PAD_499") (pintype "power_in"))
      (node (ref "U1") (pin "P$1") (pinfunction "PAD_P$1") (pintype "power_in"))
      (node (ref "U1") (pin "P$2") (pinfunction "PAD_P$2") (pintype "power_in"))
      (node (ref "U1") (pin "P$3") (pinfunction "PAD_P$3") (pintype "power_in"))
      (node (ref "U1") (pin "P$4") (pinfunction "PAD_P$4") (pintype "power_in"))
      (node (ref "U1") (pin "P$5") (pinfunction "PAD_P$5") (pintype "power_in"))
      (node (ref "U1") (pin "P$6") (pinfunction "PAD_P$6") (pintype "power_in"))
      (node (ref "U1") (pin "P$7") (pinfunction "PAD_P$7") (pintype "power_in"))
    )
    (net (code "38") (name "Net-(C31-Pad2)") (class "Default")
      (node (ref "C31") (pin "2") (pinfunction "2_2") (pintype "passive"))
      (node (ref "R22") (pin "2") (pinfunction "2_2") (pintype "passive"))
      (node (ref "R26") (pin "1") (pinfunction "1_1") (pintype "passive"))
    )
    (net (code "39") (name "Net-(C42-Pad1)") (class "Default")
      (node (ref "C42") (pin "1") (pinfunction "1_1") (pintype "passive"))
      (node (ref "L1") (pin "1") (pinfunction "1_1") (pintype "passive"))
    )
    (net (code "40") (name "Net-(C42-Pad2)") (class "Default")
      (node (ref "C42") (pin "2") (pinfunction "2_2") (pintype "passive"))
      (node (ref "R39") (pin "2") (pinfunction "2_2") (pintype "passive"))
    )
    (net (code "41") (name "Net-(C43-Pad1)") (class "Default")
      (node (ref "C43") (pin "1") (pinfunction "1_1") (pintype "passive"))
      (node (ref "L1") (pin "2") (pinfunction "2_2") (pintype "passive"))
    )
    (net (code "42") (name "Net-(C43-Pad2)") (class "Default")
      (node (ref "C43") (pin "2") (pinfunction "2_2") (pintype "passive"))
      (node (ref "R40") (pin "2") (pinfunction "2_2") (pintype "passive"))
    )
    (net (code "43") (name "Net-(C44-Pad1)") (class "Default")
      (node (ref "C44") (pin "1") (pinfunction "1_1") (pintype "passive"))
      (node (ref "L2") (pin "1") (pinfunction "1_1") (pintype "passive"))
    )
    (net (code "44") (name "Net-(C44-Pad2)") (class "Default")
      (node (ref "C44") (pin "2") (pinfunction "2_2") (pintype "passive"))
      (node (ref "R41") (pin "2") (pinfunction "2_2") (pintype "passive"))
    )
    (net (code "45") (name "Net-(C45-Pad1)") (class "Default")
      (node (ref "C45") (pin "1") (pinfunction "1_1") (pintype "passive"))
      (node (ref "L2") (pin "2") (pinfunction "2_2") (pintype "passive"))
    )
    (net (code "46") (name "Net-(C45-Pad2)") (class "Default")
      (node (ref "C45") (pin "2") (pinfunction "2_2") (pintype "passive"))
      (node (ref "R42") (pin "2") (pinfunction "2_2") (pintype "passive"))
    )
    (net (code "47") (name "Net-(C46-Pad1)") (class "Default")
      (node (ref "C46") (pin "1") (pinfunction "1_1") (pintype "passive"))
      (node (ref "L3") (pin "1") (pinfunction "1_1") (pintype "passive"))
    )
    (net (code "48") (name "Net-(C46-Pad2)") (class "Default")
      (node (ref "C46") (pin "2") (pinfunction "2_2") (pintype "passive"))
      (node (ref "R35") (pin "2") (pinfunction "2_2") (pintype "passive"))
    )
    (net (code "49") (name "Net-(C47-Pad1)") (class "Default")
      (node (ref "C47") (pin "1") (pinfunction "1_1") (pintype "passive"))
      (node (ref "L3") (pin "2") (pinfunction "2_2") (pintype "passive"))
    )
    (net (code "50") (name "Net-(C47-Pad2)") (class "Default")
      (node (ref "C47") (pin "2") (pinfunction "2_2") (pintype "passive"))
      (node (ref "R36") (pin "2") (pinfunction "2_2") (pintype "passive"))
    )
    (net (code "51") (name "Net-(C48-Pad1)") (class "Default")
      (node (ref "C48") (pin "1") (pinfunction "1_1") (pintype "passive"))
      (node (ref "L4") (pin "1") (pinfunction "1_1") (pintype "passive"))
    )
    (net (code "52") (name "Net-(C48-Pad2)") (class "Default")
      (node (ref "C48") (pin "2") (pinfunction "2_2") (pintype "passive"))
      (node (ref "R37") (pin "2") (pinfunction "2_2") (pintype "passive"))
    )
    (net (code "53") (name "Net-(C49-Pad1)") (class "Default")
      (node (ref "C49") (pin "1") (pinfunction "1_1") (pintype "passive"))
      (node (ref "L4") (pin "2") (pinfunction "2_2") (pintype "passive"))
    )
    (net (code "54") (name "Net-(C49-Pad2)") (class "Default")
      (node (ref "C49") (pin "2") (pinfunction "2_2") (pintype "passive"))
      (node (ref "R38") (pin "2") (pinfunction "2_2") (pintype "passive"))
    )
    (net (code "55") (name "Net-(D1-PadA)") (class "Default")
      (node (ref "D1") (pin "A") (pinfunction "A_A") (pintype "passive"))
      (node (ref "R1") (pin "1") (pinfunction "1_1") (pintype "passive"))
    )
    (net (code "56") (name "Net-(D2-Pad1)") (class "Default")
      (node (ref "D2") (pin "1") (pinfunction "1_1") (pintype "passive"))
      (node (ref "R31") (pin "2") (pinfunction "2_2") (pintype "passive"))
      (node (ref "R35") (pin "1") (pinfunction "1_1") (pintype "passive"))
    )
    (net (code "57") (name "Net-(D2-Pad2)") (class "Default")
      (node (ref "D2") (pin "2") (pinfunction "2_2") (pintype "passive"))
      (node (ref "R32") (pin "2") (pinfunction "2_2") (pintype "passive"))
      (node (ref "R36") (pin "1") (pinfunction "1_1") (pintype "passive"))
    )
    (net (code "58") (name "Net-(D4-Pad1)") (class "Default")
      (node (ref "D4") (pin "1") (pinfunction "1_1") (pintype "passive"))
      (node (ref "R39") (pin "1") (pinfunction "1_1") (pintype "passive"))
      (node (ref "R43") (pin "2") (pinfunction "2_2") (pintype "passive"))
    )
    (net (code "59") (name "Net-(D4-Pad2)") (class "Default")
      (node (ref "D4") (pin "2") (pinfunction "2_2") (pintype "passive"))
      (node (ref "R40") (pin "1") (pinfunction "1_1") (pintype "passive"))
      (node (ref "R44") (pin "2") (pinfunction "2_2") (pintype "passive"))
    )
    (net (code "60") (name "Net-(R10-Pad1)") (class "Default")
      (node (ref "R10") (pin "1") (pinfunction "1_1") (pintype "passive"))
      (node (ref "R9") (pin "1") (pinfunction "1_1") (pintype "passive"))
    )
    (net (code "61") (name "Net-(R33-Pad2)") (class "Default")
      (node (ref "R33") (pin "2") (pinfunction "2_2") (pintype "passive"))
      (node (ref "R37") (pin "1") (pinfunction "1_1") (pintype "passive"))
    )
    (net (code "62") (name "Net-(R34-Pad2)") (class "Default")
      (node (ref "R34") (pin "2") (pinfunction "2_2") (pintype "passive"))
      (node (ref "R38") (pin "1") (pinfunction "1_1") (pintype "passive"))
    )
    (net (code "63") (name "Net-(R41-Pad1)") (class "Default")
      (node (ref "R41") (pin "1") (pinfunction "1_1") (pintype "passive"))
      (node (ref "R45") (pin "2") (pinfunction "2_2") (pintype "passive"))
    )
    (net (code "64") (name "Net-(R42-Pad1)") (class "Default")
      (node (ref "R42") (pin "1") (pinfunction "1_1") (pintype "passive"))
      (node (ref "R46") (pin "2") (pinfunction "2_2") (pintype "passive"))
    )
    (net (code "65") (name "Net-(U1-BAT)") (class "Default")
      (node (ref "R18") (pin "1") (pinfunction "1_1") (pintype "passive"))
      (node (ref "U1") (pin "48") (pinfunction "BAT_48") (pintype "input"))
    )
    (net (code "66") (name "Net-(U1-DVDD)") (class "Default")
      (node (ref "C34") (pin "1") (pinfunction "1_1") (pintype "passive"))
      (node (ref "U1") (pin "36") (pinfunction "DVDD_36") (pintype "power_in"))
    )
    (net (code "67") (name "Net-(U1-LDOIN)") (class "Default")
      (node (ref "R28") (pin "1") (pinfunction "1_1") (pintype "passive"))
      (node (ref "U1") (pin "37") (pinfunction "LDOIN_37") (pintype "input"))
    )
    (net (code "68") (name "Net-(U1-VC0)") (class "Default")
      (node (ref "C12") (pin "1") (pinfunction "1_1") (pintype "passive"))
      (node (ref "C16") (pin "2") (pinfunction "2_2") (pintype "passive"))
      (node (ref "R8") (pin "2") (pinfunction "2_2") (pintype "passive"))
      (node (ref "U1") (pin "14") (pinfunction "VC0_14") (pintype "input"))
    )
    (net (code "69") (name "Net-(U1-VC1)") (class "Default")
      (node (ref "C12") (pin "2") (pinfunction "2_2") (pintype "passive"))
      (node (ref "C15") (pin "1") (pinfunction "1_1") (pintype "passive"))
      (node (ref "C27") (pin "1") (pinfunction "1_1") (pintype "passive"))
      (node (ref "R7") (pin "2") (pinfunction "2_2") (pintype "passive"))
      (node (ref "U1") (pin "12") (pinfunction "VC1_12") (pintype "input"))
    )
    (net (code "70") (name "Net-(U1-VC2)") (class "Default")
      (node (ref "C11") (pin "1") (pinfunction "1_1") (pintype "passive"))
      (node (ref "C15") (pin "2") (pinfunction "2_2") (pintype "passive"))
      (node (ref "C27") (pin "2") (pinfunction "2_2") (pintype "passive"))
      (node (ref "R6") (pin "2") (pinfunction "2_2") (pintype "passive"))
      (node (ref "U1") (pin "10") (pinfunction "VC2_10") (pintype "input"))
    )
    (net (code "71") (name "Net-(U1-VC3)") (class "Default")
      (node (ref "C11") (pin "2") (pinfunction "2_2") (pintype "passive"))
      (node (ref "C14") (pin "1") (pinfunction "1_1") (pintype "passive"))
      (node (ref "R5") (pin "2") (pinfunction "2_2") (pintype "passive"))
      (node (ref "U1") (pin "8") (pinfunction "VC3_8") (pintype "input"))
    )
    (net (code "72") (name "Net-(U1-VC4)") (class "Default")
      (node (ref "C10") (pin "1") (pinfunction "1_1") (pintype "passive"))
      (node (ref "C14") (pin "2") (pinfunction "2_2") (pintype "passive"))
      (node (ref "C26") (pin "1") (pinfunction "1_1") (pintype "passive"))
      (node (ref "R4") (pin "2") (pinfunction "2_2") (pintype "passive"))
      (node (ref "U1") (pin "6") (pinfunction "VC4_6") (pintype "input"))
    )
    (net (code "73") (name "Net-(U1-VC5)") (class "Default")
      (node (ref "C10") (pin "2") (pinfunction "2_2") (pintype "passive"))
      (node (ref "C13") (pin "1") (pinfunction "1_1") (pintype "passive"))
      (node (ref "C26") (pin "2") (pinfunction "2_2") (pintype "passive"))
      (node (ref "R3") (pin "2") (pinfunction "2_2") (pintype "passive"))
      (node (ref "U1") (pin "4") (pinfunction "VC5_4") (pintype "input"))
    )
    (net (code "74") (name "Net-(U1-VC6)") (class "Default")
      (node (ref "C13") (pin "2") (pinfunction "2_2") (pintype "passive"))
      (node (ref "R2") (pin "2") (pinfunction "2_2") (pintype "passive"))
      (node (ref "U1") (pin "2") (pinfunction "VC6_2") (pintype "input"))
    )
    (net (code "75") (name "VCC") (class "Default")
      (node (ref "C21") (pin "1") (pinfunction "1_1") (pintype "passive"))
      (node (ref "C36") (pin "1") (pinfunction "1_1") (pintype "passive"))
      (node (ref "C4") (pin "2") (pinfunction "2_2") (pintype "passive"))
      (node (ref "R11") (pin "1") (pinfunction "1_1") (pintype "passive"))
      (node (ref "R18") (pin "2") (pinfunction "2_2") (pintype "passive"))
      (node (ref "R2") (pin "1") (pinfunction "1_1") (pintype "passive"))
      (node (ref "R28") (pin "2") (pinfunction "2_2") (pintype "passive"))
    )
    (net (code "76") (name "unconnected-(D3-Pad1)") (class "Default")
      (node (ref "D3") (pin "1") (pinfunction "1_1") (pintype "passive"))
    )
    (net (code "77") (name "unconnected-(D3-Pad2)") (class "Default")
      (node (ref "D3") (pin "2") (pinfunction "2_2") (pintype "passive"))
    )
    (net (code "78") (name "unconnected-(D5-Pad1)") (class "Default")
      (node (ref "D5") (pin "1") (pinfunction "1_1") (pintype "passive"))
    )
    (net (code "79") (name "unconnected-(D5-Pad2)") (class "Default")
      (node (ref "D5") (pin "2") (pinfunction "2_2") (pintype "passive"))
    )
    (net (code "80") (name "unconnected-(L1-Pad3)") (class "Default")
      (node (ref "L1") (pin "3") (pinfunction "3_3") (pintype "passive"))
    )
    (net (code "81") (name "unconnected-(L1-Pad4)") (class "Default")
      (node (ref "L1") (pin "4") (pinfunction "4_4") (pintype "passive"))
    )
    (net (code "82") (name "unconnected-(L2-Pad3)") (class "Default")
      (node (ref "L2") (pin "3") (pinfunction "3_3") (pintype "passive"))
    )
    (net (code "83") (name "unconnected-(L2-Pad4)") (class "Default")
      (node (ref "L2") (pin "4") (pinfunction "4_4") (pintype "passive"))
    )
    (net (code "84") (name "unconnected-(L3-Pad3)") (class "Default")
      (node (ref "L3") (pin "3") (pinfunction "3_3") (pintype "passive"))
    )
    (net (code "85") (name "unconnected-(L3-Pad4)") (class "Default")
      (node (ref "L3") (pin "4") (pinfunction "4_4") (pintype "passive"))
    )
    (net (code "86") (name "unconnected-(L4-Pad3)") (class "Default")
      (node (ref "L4") (pin "3") (pinfunction "3_3") (pintype "passive"))
    )
    (net (code "87") (name "unconnected-(L4-Pad4)") (class "Default")
      (node (ref "L4") (pin "4") (pinfunction "4_4") (pintype "passive"))
    )
    (net (code "88") (name "unconnected-(U1-NC-Pad38)") (class "Default")
      (node (ref "U1") (pin "38") (pinfunction "NC_38") (pintype "no_connect"))
    )
    (net (code "89") (name "unconnected-(U1-NC-Pad47)") (class "Default")
      (node (ref "U1") (pin "47") (pinfunction "NC_47") (pintype "no_connect"))
    )
  )
)
